# ps2.net
KiCad netlist of a schematic drawn in EAGLE
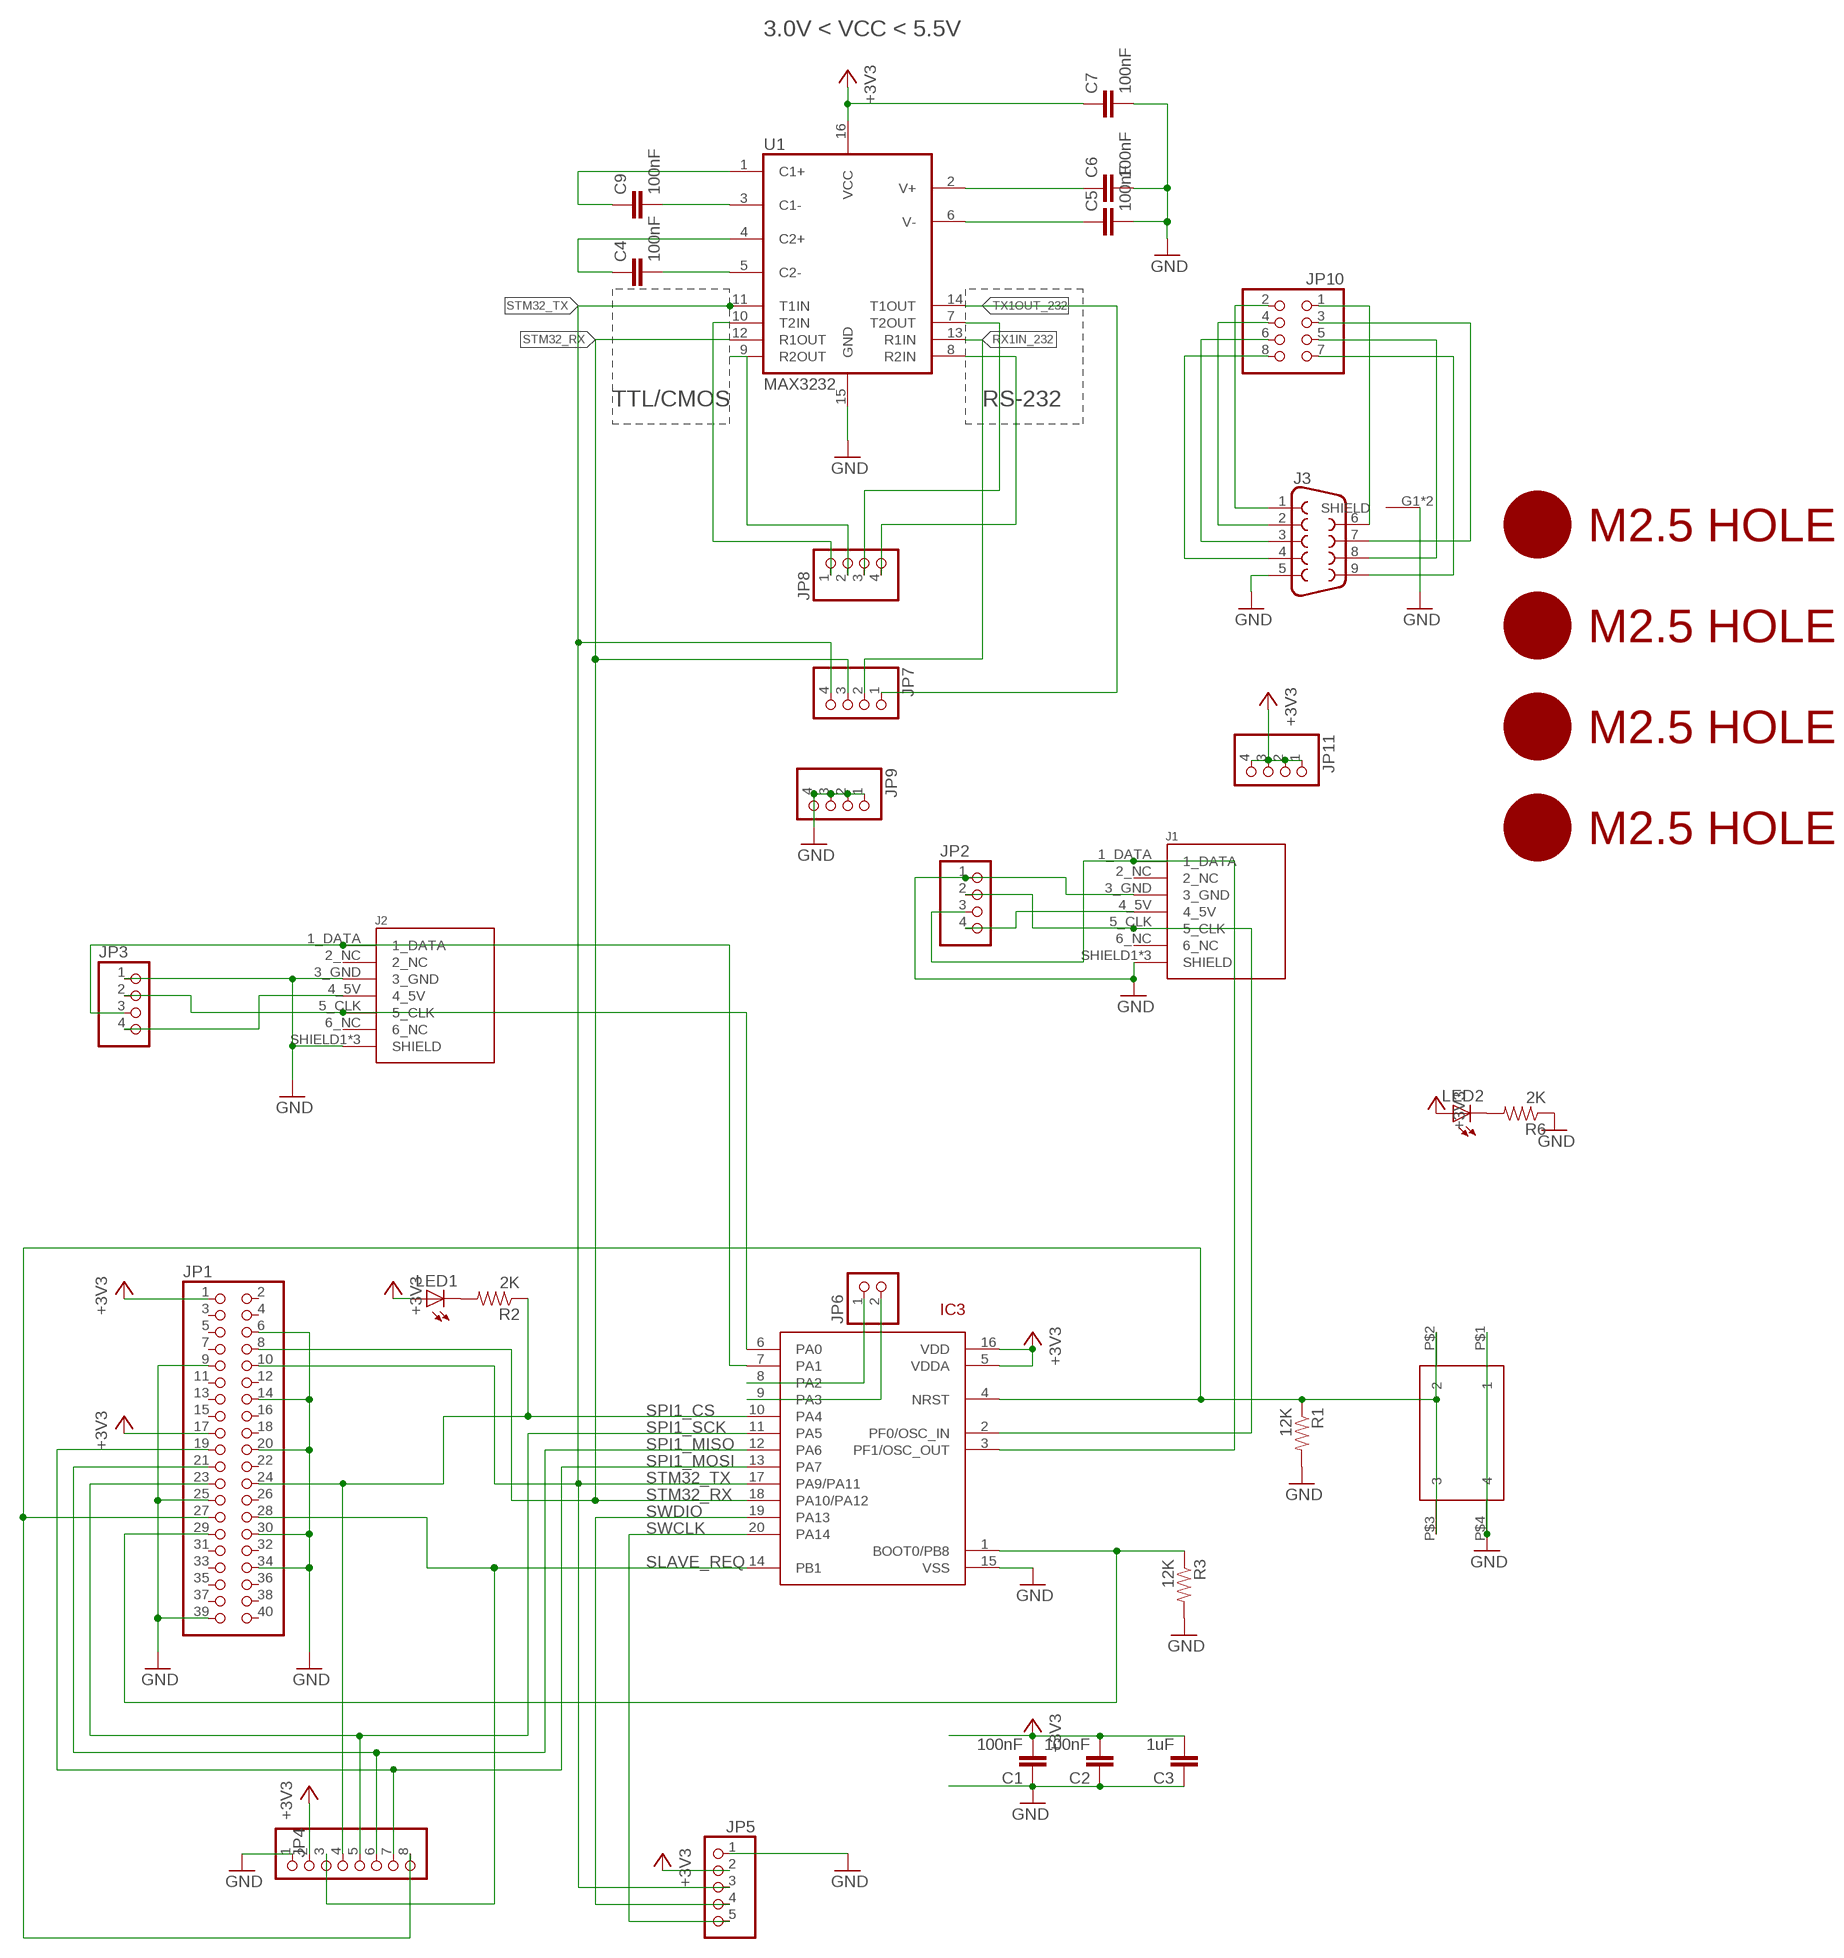
[diagram p0: schematic, sheet 1]

(export (version "E")
  (design (tool "Eeschema 10.0.6"))
  (components
    (comp (ref "C1")
      (value "100nF")
      (footprint "eagle-import:0805@1")
      (libsource (lib "eagle-import") (part "CAP0805"))
    )
    (comp (ref "C2")
      (value "100nF")
      (footprint "eagle-import:0805@1")
      (libsource (lib "eagle-import") (part "CAP0805"))
    )
    (comp (ref "C3")
      (value "1uF")
      (footprint "eagle-import:0805@1")
      (libsource (lib "eagle-import") (part "CAP0805"))
    )
    (comp (ref "C4")
      (value "100nF")
      (footprint "eagle-import:0805@1")
      (libsource (lib "eagle-import") (part "CAP0805"))
    )
    (comp (ref "C5")
      (value "100nF")
      (footprint "eagle-import:0805@1")
      (libsource (lib "eagle-import") (part "CAP0805"))
    )
    (comp (ref "C6")
      (value "100nF")
      (footprint "eagle-import:0805@1")
      (libsource (lib "eagle-import") (part "CAP0805"))
    )
    (comp (ref "C7")
      (value "100nF")
      (footprint "eagle-import:0805@1")
      (libsource (lib "eagle-import") (part "CAP0805"))
    )
    (comp (ref "C9")
      (value "100nF")
      (footprint "eagle-import:0805@1")
      (libsource (lib "eagle-import") (part "CAP0805"))
    )
    (comp (ref "IC3")
      (value "STM32F042F4")
      (footprint "eagle-import:TSSOP20")
      (libsource (lib "eagle-import") (part "STM32F042F4"))
    )
    (comp (ref "J1")
      (value "DIN7")
      (footprint "eagle-import:DIN7")
      (libsource (lib "eagle-import") (part "DIN7"))
    )
    (comp (ref "J2")
      (value "DIN7")
      (footprint "eagle-import:DIN7")
      (libsource (lib "eagle-import") (part "DIN7"))
    )
    (comp (ref "J3")
      (value "DB9MALE")
      (footprint "eagle-import:DB9_MALE")
      (libsource (lib "eagle-import") (part "DB9MALE"))
    )
    (comp (ref "JP1")
      (value "PINHD-2X20-BIG")
      (footprint "eagle-import:2X20-BIG")
      (libsource (lib "eagle-import") (part "PINHD-2X20-BIG"))
    )
    (comp (ref "JP2")
      (value "PINHD-1X4")
      (footprint "eagle-import:1X04")
      (libsource (lib "eagle-import") (part "PINHD-1X4"))
    )
    (comp (ref "JP3")
      (value "PINHD-1X4")
      (footprint "eagle-import:1X04")
      (libsource (lib "eagle-import") (part "PINHD-1X4"))
    )
    (comp (ref "JP4")
      (value "PINHD-1X8")
      (footprint "eagle-import:1X08")
      (libsource (lib "eagle-import") (part "PINHD-1X8"))
    )
    (comp (ref "JP5")
      (value "PINHD-1X5")
      (footprint "eagle-import:1X05")
      (libsource (lib "eagle-import") (part "PINHD-1X5"))
    )
    (comp (ref "JP6")
      (value "PINHD-1X2")
      (footprint "eagle-import:1X02")
      (libsource (lib "eagle-import") (part "PINHD-1X2"))
    )
    (comp (ref "JP7")
      (value "PINHD-1X4")
      (footprint "eagle-import:1X04")
      (libsource (lib "eagle-import") (part "PINHD-1X4"))
    )
    (comp (ref "JP8")
      (value "PINHD-1X4")
      (footprint "eagle-import:1X04")
      (libsource (lib "eagle-import") (part "PINHD-1X4"))
    )
    (comp (ref "JP9")
      (value "PINHD-1X4")
      (footprint "eagle-import:1X04")
      (libsource (lib "eagle-import") (part "PINHD-1X4"))
    )
    (comp (ref "JP10")
      (value "PINHD-2X4")
      (footprint "eagle-import:2X04")
      (libsource (lib "eagle-import") (part "PINHD-2X4"))
    )
    (comp (ref "JP11")
      (value "PINHD-1X4")
      (footprint "eagle-import:1X04")
      (libsource (lib "eagle-import") (part "PINHD-1X4"))
    )
    (comp (ref "LED1")
      (value "LEDCHIP-LED0805")
      (footprint "eagle-import:CHIP-LED0805")
      (libsource (lib "eagle-import") (part "LEDCHIP-LED0805"))
    )
    (comp (ref "LED2")
      (value "LEDCHIP-LED0805")
      (footprint "eagle-import:CHIP-LED0805")
      (libsource (lib "eagle-import") (part "LEDCHIP-LED0805"))
    )
    (comp (ref "R1")
      (value "12K")
      (footprint "eagle-import:0805")
      (libsource (lib "eagle-import") (part "RESISTOR0805-RES"))
    )
    (comp (ref "R2")
      (value "2K")
      (footprint "eagle-import:0805")
      (libsource (lib "eagle-import") (part "RESISTOR0805-RES"))
    )
    (comp (ref "R3")
      (value "12K")
      (footprint "eagle-import:0805")
      (libsource (lib "eagle-import") (part "RESISTOR0805-RES"))
    )
    (comp (ref "R6")
      (value "2K")
      (footprint "eagle-import:0805")
      (libsource (lib "eagle-import") (part "RESISTOR0805-RES"))
    )
    (comp (ref "SW4")
      (value "324_SW")
      (footprint "eagle-import:342_SWICH_FOOT")
      (libsource (lib "eagle-import") (part "324_SW"))
    )
    (comp (ref "U$2")
      (value "M2.5HOLE")
      (footprint "eagle-import:M2.5HOLE")
      (libsource (lib "eagle-import") (part "M2.5HOLE"))
    )
    (comp (ref "U$3")
      (value "M2.5HOLE")
      (footprint "eagle-import:M2.5HOLE")
      (libsource (lib "eagle-import") (part "M2.5HOLE"))
    )
    (comp (ref "U$4")
      (value "M2.5HOLE")
      (footprint "eagle-import:M2.5HOLE")
      (libsource (lib "eagle-import") (part "M2.5HOLE"))
    )
    (comp (ref "U$5")
      (value "M2.5HOLE")
      (footprint "eagle-import:M2.5HOLE")
      (libsource (lib "eagle-import") (part "M2.5HOLE"))
    )
    (comp (ref "U1")
      (value "MAX3232")
      (footprint "eagle-import:SO016")
      (libsource (lib "eagle-import") (part "MAX232SOIC16"))
    )
  )
  (nets
    (net (code "1") (name "+3V3") (class "Default")
      (node (ref "C1") (pin "2") (pinfunction "2_2") (pintype "passive"))
      (node (ref "C2") (pin "2") (pinfunction "2_2") (pintype "passive"))
      (node (ref "C3") (pin "2") (pinfunction "2_2") (pintype "passive"))
      (node (ref "C7") (pin "1") (pinfunction "1_1") (pintype "passive"))
      (node (ref "IC3") (pin "16") (pinfunction "VDD_16") (pintype "bidirectional"))
      (node (ref "IC3") (pin "5") (pinfunction "VDDA_5") (pintype "bidirectional"))
      (node (ref "JP1") (pin "1") (pinfunction "1_1") (pintype "passive"))
      (node (ref "JP1") (pin "17") (pinfunction "17_17") (pintype "passive"))
      (node (ref "JP11") (pin "1") (pinfunction "1_1") (pintype "passive"))
      (node (ref "JP11") (pin "2") (pinfunction "2_2") (pintype "passive"))
      (node (ref "JP11") (pin "3") (pinfunction "3_3") (pintype "passive"))
      (node (ref "JP11") (pin "4") (pinfunction "4_4") (pintype "passive"))
      (node (ref "JP4") (pin "2") (pinfunction "2_2") (pintype "passive"))
      (node (ref "JP5") (pin "2") (pinfunction "2_2") (pintype "passive"))
      (node (ref "LED1") (pin "A") (pinfunction "A_A") (pintype "passive"))
      (node (ref "LED2") (pin "A") (pinfunction "A_A") (pintype "passive"))
      (node (ref "U1") (pin "16") (pinfunction "VCC_16") (pintype "bidirectional"))
    )
    (net (code "2") (name "/SLAVE_REQ") (class "Default")
      (node (ref "IC3") (pin "14") (pinfunction "PB1_14") (pintype "bidirectional"))
      (node (ref "JP1") (pin "28") (pinfunction "28_28") (pintype "passive"))
      (node (ref "JP4") (pin "3") (pinfunction "3_3") (pintype "passive"))
    )
    (net (code "3") (name "/SPI1_CS") (class "Default")
      (node (ref "IC3") (pin "10") (pinfunction "PA4_10") (pintype "bidirectional"))
      (node (ref "JP1") (pin "24") (pinfunction "24_24") (pintype "passive"))
      (node (ref "JP4") (pin "4") (pinfunction "4_4") (pintype "passive"))
      (node (ref "R2") (pin "1") (pinfunction "1_1") (pintype "passive"))
    )
    (net (code "4") (name "/SPI1_MISO") (class "Default")
      (node (ref "IC3") (pin "12") (pinfunction "PA6_12") (pintype "bidirectional"))
      (node (ref "JP1") (pin "21") (pinfunction "21_21") (pintype "passive"))
      (node (ref "JP4") (pin "6") (pinfunction "6_6") (pintype "passive"))
    )
    (net (code "5") (name "/SPI1_MOSI") (class "Default")
      (node (ref "IC3") (pin "13") (pinfunction "PA7_13") (pintype "bidirectional"))
      (node (ref "JP1") (pin "19") (pinfunction "19_19") (pintype "passive"))
      (node (ref "JP4") (pin "7") (pinfunction "7_7") (pintype "passive"))
    )
    (net (code "6") (name "/SPI1_SCK") (class "Default")
      (node (ref "IC3") (pin "11") (pinfunction "PA5_11") (pintype "bidirectional"))
      (node (ref "JP1") (pin "23") (pinfunction "23_23") (pintype "passive"))
      (node (ref "JP4") (pin "5") (pinfunction "5_5") (pintype "passive"))
    )
    (net (code "7") (name "/SWCLK") (class "Default")
      (node (ref "IC3") (pin "20") (pinfunction "PA14_20") (pintype "bidirectional"))
      (node (ref "JP5") (pin "5") (pinfunction "5_5") (pintype "passive"))
    )
    (net (code "8") (name "/SWDIO") (class "Default")
      (node (ref "IC3") (pin "19") (pinfunction "PA13_19") (pintype "bidirectional"))
      (node (ref "JP5") (pin "4") (pinfunction "4_4") (pintype "passive"))
    )
    (net (code "9") (name "GND") (class "Default")
      (node (ref "C1") (pin "1") (pinfunction "1_1") (pintype "passive"))
      (node (ref "C2") (pin "1") (pinfunction "1_1") (pintype "passive"))
      (node (ref "C3") (pin "1") (pinfunction "1_1") (pintype "passive"))
      (node (ref "C5") (pin "2") (pinfunction "2_2") (pintype "passive"))
      (node (ref "C6") (pin "2") (pinfunction "2_2") (pintype "passive"))
      (node (ref "C7") (pin "2") (pinfunction "2_2") (pintype "passive"))
      (node (ref "IC3") (pin "15") (pinfunction "VSS_15") (pintype "bidirectional"))
      (node (ref "J1") (pin "3_GND") (pinfunction "3_GND_3_GND") (pintype "bidirectional"))
      (node (ref "J1") (pin "SHIELD1") (pinfunction "SHIELD_SHIELD1") (pintype "bidirectional"))
      (node (ref "J1") (pin "SHIELD2") (pinfunction "SHIELD_SHIELD2") (pintype "bidirectional"))
      (node (ref "J1") (pin "SHIELD3") (pinfunction "SHIELD_SHIELD3") (pintype "bidirectional"))
      (node (ref "J2") (pin "3_GND") (pinfunction "3_GND_3_GND") (pintype "bidirectional"))
      (node (ref "J2") (pin "SHIELD1") (pinfunction "SHIELD_SHIELD1") (pintype "bidirectional"))
      (node (ref "J2") (pin "SHIELD2") (pinfunction "SHIELD_SHIELD2") (pintype "bidirectional"))
      (node (ref "J2") (pin "SHIELD3") (pinfunction "SHIELD_SHIELD3") (pintype "bidirectional"))
      (node (ref "J3") (pin "5") (pinfunction "5_5") (pintype "passive"))
      (node (ref "J3") (pin "G1") (pinfunction "SHIELD_G1") (pintype "bidirectional"))
      (node (ref "J3") (pin "G2") (pinfunction "SHIELD_G2") (pintype "bidirectional"))
      (node (ref "JP1") (pin "14") (pinfunction "14_14") (pintype "passive"))
      (node (ref "JP1") (pin "20") (pinfunction "20_20") (pintype "passive"))
      (node (ref "JP1") (pin "25") (pinfunction "25_25") (pintype "passive"))
      (node (ref "JP1") (pin "30") (pinfunction "30_30") (pintype "passive"))
      (node (ref "JP1") (pin "34") (pinfunction "34_34") (pintype "passive"))
      (node (ref "JP1") (pin "39") (pinfunction "39_39") (pintype "passive"))
      (node (ref "JP1") (pin "6") (pinfunction "6_6") (pintype "passive"))
      (node (ref "JP1") (pin "9") (pinfunction "9_9") (pintype "passive"))
      (node (ref "JP2") (pin "1") (pinfunction "1_1") (pintype "passive"))
      (node (ref "JP3") (pin "1") (pinfunction "1_1") (pintype "passive"))
      (node (ref "JP4") (pin "1") (pinfunction "1_1") (pintype "passive"))
      (node (ref "JP5") (pin "1") (pinfunction "1_1") (pintype "passive"))
      (node (ref "JP9") (pin "1") (pinfunction "1_1") (pintype "passive"))
      (node (ref "JP9") (pin "2") (pinfunction "2_2") (pintype "passive"))
      (node (ref "JP9") (pin "3") (pinfunction "3_3") (pintype "passive"))
      (node (ref "JP9") (pin "4") (pinfunction "4_4") (pintype "passive"))
      (node (ref "R1") (pin "2") (pinfunction "2_2") (pintype "passive"))
      (node (ref "R3") (pin "2") (pinfunction "2_2") (pintype "passive"))
      (node (ref "R6") (pin "1") (pinfunction "1_1") (pintype "passive"))
      (node (ref "SW4") (pin "P$1") (pinfunction "1_P$1") (pintype "bidirectional"))
      (node (ref "SW4") (pin "P$4") (pinfunction "4_P$4") (pintype "bidirectional"))
      (node (ref "U1") (pin "15") (pinfunction "GND_15") (pintype "bidirectional"))
    )
    (net (code "10") (name "Net-(IC3-BOOT0{slash}PB8)") (class "Default")
      (node (ref "IC3") (pin "1") (pinfunction "BOOT0/PB8_1") (pintype "bidirectional"))
      (node (ref "JP1") (pin "29") (pinfunction "29_29") (pintype "passive"))
      (node (ref "R3") (pin "1") (pinfunction "1_1") (pintype "passive"))
    )
    (net (code "11") (name "Net-(IC3-NRST)") (class "Default")
      (node (ref "IC3") (pin "4") (pinfunction "NRST_4") (pintype "bidirectional"))
      (node (ref "JP1") (pin "27") (pinfunction "27_27") (pintype "passive"))
      (node (ref "JP4") (pin "8") (pinfunction "8_8") (pintype "passive"))
      (node (ref "R1") (pin "1") (pinfunction "1_1") (pintype "passive"))
      (node (ref "SW4") (pin "P$2") (pinfunction "2_P$2") (pintype "bidirectional"))
      (node (ref "SW4") (pin "P$3") (pinfunction "3_P$3") (pintype "bidirectional"))
    )
    (net (code "12") (name "Net-(IC3-PA0)") (class "Default")
      (node (ref "IC3") (pin "6") (pinfunction "PA0_6") (pintype "bidirectional"))
      (node (ref "J2") (pin "5_CLK") (pinfunction "5_CLK_5_CLK") (pintype "bidirectional"))
      (node (ref "JP3") (pin "2") (pinfunction "2_2") (pintype "passive"))
    )
    (net (code "13") (name "Net-(IC3-PA1)") (class "Default")
      (node (ref "IC3") (pin "7") (pinfunction "PA1_7") (pintype "bidirectional"))
      (node (ref "J2") (pin "1_DATA") (pinfunction "1_DATA_1_DATA") (pintype "bidirectional"))
      (node (ref "JP3") (pin "3") (pinfunction "3_3") (pintype "passive"))
    )
    (net (code "14") (name "Net-(IC3-PA2)") (class "Default")
      (node (ref "IC3") (pin "8") (pinfunction "PA2_8") (pintype "bidirectional"))
      (node (ref "JP6") (pin "1") (pinfunction "1_1") (pintype "passive"))
    )
    (net (code "15") (name "Net-(IC3-PA3)") (class "Default")
      (node (ref "IC3") (pin "9") (pinfunction "PA3_9") (pintype "bidirectional"))
      (node (ref "JP6") (pin "2") (pinfunction "2_2") (pintype "passive"))
    )
    (net (code "16") (name "Net-(IC3-PF0{slash}OSC_IN)") (class "Default")
      (node (ref "IC3") (pin "2") (pinfunction "PF0/OSC_IN_2") (pintype "bidirectional"))
      (node (ref "J1") (pin "5_CLK") (pinfunction "5_CLK_5_CLK") (pintype "bidirectional"))
      (node (ref "JP2") (pin "2") (pinfunction "2_2") (pintype "passive"))
    )
    (net (code "17") (name "Net-(IC3-PF1{slash}OSC_OUT)") (class "Default")
      (node (ref "IC3") (pin "3") (pinfunction "PF1/OSC_OUT_3") (pintype "bidirectional"))
      (node (ref "J1") (pin "1_DATA") (pinfunction "1_DATA_1_DATA") (pintype "bidirectional"))
      (node (ref "JP2") (pin "3") (pinfunction "3_3") (pintype "passive"))
    )
    (net (code "18") (name "Net-(J1-Pad4_5V)") (class "Default")
      (node (ref "J1") (pin "4_5V") (pinfunction "4_5V_4_5V") (pintype "bidirectional"))
      (node (ref "JP2") (pin "4") (pinfunction "4_4") (pintype "passive"))
    )
    (net (code "19") (name "Net-(J2-Pad4_5V)") (class "Default")
      (node (ref "J2") (pin "4_5V") (pinfunction "4_5V_4_5V") (pintype "bidirectional"))
      (node (ref "JP3") (pin "4") (pinfunction "4_4") (pintype "passive"))
    )
    (net (code "20") (name "Net-(J3-Pad1)") (class "Default")
      (node (ref "J3") (pin "1") (pinfunction "1_1") (pintype "passive"))
      (node (ref "JP10") (pin "2") (pinfunction "2_2") (pintype "passive"))
    )
    (net (code "21") (name "Net-(J3-Pad2)") (class "Default")
      (node (ref "J3") (pin "2") (pinfunction "2_2") (pintype "passive"))
      (node (ref "JP10") (pin "4") (pinfunction "4_4") (pintype "passive"))
    )
    (net (code "22") (name "Net-(J3-Pad3)") (class "Default")
      (node (ref "J3") (pin "3") (pinfunction "3_3") (pintype "passive"))
      (node (ref "JP10") (pin "6") (pinfunction "6_6") (pintype "passive"))
    )
    (net (code "23") (name "Net-(J3-Pad4)") (class "Default")
      (node (ref "J3") (pin "4") (pinfunction "4_4") (pintype "passive"))
      (node (ref "JP10") (pin "8") (pinfunction "8_8") (pintype "passive"))
    )
    (net (code "24") (name "Net-(J3-Pad6)") (class "Default")
      (node (ref "J3") (pin "6") (pinfunction "6_6") (pintype "passive"))
      (node (ref "JP10") (pin "1") (pinfunction "1_1") (pintype "passive"))
    )
    (net (code "25") (name "Net-(J3-Pad7)") (class "Default")
      (node (ref "J3") (pin "7") (pinfunction "7_7") (pintype "passive"))
      (node (ref "JP10") (pin "3") (pinfunction "3_3") (pintype "passive"))
    )
    (net (code "26") (name "Net-(J3-Pad8)") (class "Default")
      (node (ref "J3") (pin "8") (pinfunction "8_8") (pintype "passive"))
      (node (ref "JP10") (pin "5") (pinfunction "5_5") (pintype "passive"))
    )
    (net (code "27") (name "Net-(J3-Pad9)") (class "Default")
      (node (ref "J3") (pin "9") (pinfunction "9_9") (pintype "passive"))
      (node (ref "JP10") (pin "7") (pinfunction "7_7") (pintype "passive"))
    )
    (net (code "28") (name "Net-(LED1-PadC)") (class "Default")
      (node (ref "LED1") (pin "C") (pinfunction "C_C") (pintype "passive"))
      (node (ref "R2") (pin "2") (pinfunction "2_2") (pintype "passive"))
    )
    (net (code "29") (name "Net-(LED2-PadC)") (class "Default")
      (node (ref "LED2") (pin "C") (pinfunction "C_C") (pintype "passive"))
      (node (ref "R6") (pin "2") (pinfunction "2_2") (pintype "passive"))
    )
    (net (code "30") (name "Net-(U1-C1+)") (class "Default")
      (node (ref "C9") (pin "1") (pinfunction "1_1") (pintype "passive"))
      (node (ref "U1") (pin "1") (pinfunction "C1+_1") (pintype "bidirectional"))
    )
    (net (code "31") (name "Net-(U1-C1-)") (class "Default")
      (node (ref "C9") (pin "2") (pinfunction "2_2") (pintype "passive"))
      (node (ref "U1") (pin "3") (pinfunction "C1-_3") (pintype "bidirectional"))
    )
    (net (code "32") (name "Net-(U1-C2+)") (class "Default")
      (node (ref "C4") (pin "1") (pinfunction "1_1") (pintype "passive"))
      (node (ref "U1") (pin "4") (pinfunction "C2+_4") (pintype "bidirectional"))
    )
    (net (code "33") (name "Net-(U1-C2-)") (class "Default")
      (node (ref "C4") (pin "2") (pinfunction "2_2") (pintype "passive"))
      (node (ref "U1") (pin "5") (pinfunction "C2-_5") (pintype "bidirectional"))
    )
    (net (code "34") (name "Net-(U1-R2IN)") (class "Default")
      (node (ref "JP8") (pin "4") (pinfunction "4_4") (pintype "passive"))
      (node (ref "U1") (pin "8") (pinfunction "R2IN_8") (pintype "input"))
    )
    (net (code "35") (name "Net-(U1-R2OUT)") (class "Default")
      (node (ref "JP8") (pin "2") (pinfunction "2_2") (pintype "passive"))
      (node (ref "U1") (pin "9") (pinfunction "R2OUT_9") (pintype "output"))
    )
    (net (code "36") (name "Net-(U1-T2IN)") (class "Default")
      (node (ref "JP8") (pin "1") (pinfunction "1_1") (pintype "passive"))
      (node (ref "U1") (pin "10") (pinfunction "T2IN_10") (pintype "input"))
    )
    (net (code "37") (name "Net-(U1-T2OUT)") (class "Default")
      (node (ref "JP8") (pin "3") (pinfunction "3_3") (pintype "passive"))
      (node (ref "U1") (pin "7") (pinfunction "T2OUT_7") (pintype "output"))
    )
    (net (code "38") (name "Net-(U1-V+)") (class "Default")
      (node (ref "C6") (pin "1") (pinfunction "1_1") (pintype "passive"))
      (node (ref "U1") (pin "2") (pinfunction "V+_2") (pintype "bidirectional"))
    )
    (net (code "39") (name "Net-(U1-V-)") (class "Default")
      (node (ref "C5") (pin "1") (pinfunction "1_1") (pintype "passive"))
      (node (ref "U1") (pin "6") (pinfunction "V-_6") (pintype "bidirectional"))
    )
    (net (code "40") (name "RX1IN_232") (class "Default")
      (node (ref "JP7") (pin "2") (pinfunction "2_2") (pintype "passive"))
      (node (ref "U1") (pin "13") (pinfunction "R1IN_13") (pintype "input"))
    )
    (net (code "41") (name "STM32_RX") (class "Default")
      (node (ref "IC3") (pin "18") (pinfunction "PA10/PA12_18") (pintype "bidirectional"))
      (node (ref "JP1") (pin "8") (pinfunction "8_8") (pintype "passive"))
      (node (ref "JP7") (pin "3") (pinfunction "3_3") (pintype "passive"))
      (node (ref "U1") (pin "12") (pinfunction "R1OUT_12") (pintype "output"))
    )
    (net (code "42") (name "STM32_TX") (class "Default")
      (node (ref "IC3") (pin "17") (pinfunction "PA9/PA11_17") (pintype "bidirectional"))
      (node (ref "JP1") (pin "10") (pinfunction "10_10") (pintype "passive"))
      (node (ref "JP5") (pin "3") (pinfunction "3_3") (pintype "passive"))
      (node (ref "JP7") (pin "4") (pinfunction "4_4") (pintype "passive"))
      (node (ref "U1") (pin "11") (pinfunction "T1IN_11") (pintype "input"))
    )
    (net (code "43") (name "TX1OUT_232") (class "Default")
      (node (ref "JP7") (pin "1") (pinfunction "1_1") (pintype "passive"))
      (node (ref "U1") (pin "14") (pinfunction "T1OUT_14") (pintype "output"))
    )
    (net (code "44") (name "unconnected-(J1-Pad2_NC)") (class "Default")
      (node (ref "J1") (pin "2_NC") (pinfunction "2_NC_2_NC") (pintype "bidirectional"))
    )
    (net (code "45") (name "unconnected-(J1-Pad6_NC)") (class "Default")
      (node (ref "J1") (pin "6_NC") (pinfunction "6_NC_6_NC") (pintype "bidirectional"))
    )
    (net (code "46") (name "unconnected-(J2-Pad2_NC)") (class "Default")
      (node (ref "J2") (pin "2_NC") (pinfunction "2_NC_2_NC") (pintype "bidirectional"))
    )
    (net (code "47") (name "unconnected-(J2-Pad6_NC)") (class "Default")
      (node (ref "J2") (pin "6_NC") (pinfunction "6_NC_6_NC") (pintype "bidirectional"))
    )
    (net (code "48") (name "unconnected-(JP1-Pad2)") (class "Default")
      (node (ref "JP1") (pin "2") (pinfunction "2_2") (pintype "passive"))
    )
    (net (code "49") (name "unconnected-(JP1-Pad3)") (class "Default")
      (node (ref "JP1") (pin "3") (pinfunction "3_3") (pintype "passive"))
    )
    (net (code "50") (name "unconnected-(JP1-Pad4)") (class "Default")
      (node (ref "JP1") (pin "4") (pinfunction "4_4") (pintype "passive"))
    )
    (net (code "51") (name "unconnected-(JP1-Pad5)") (class "Default")
      (node (ref "JP1") (pin "5") (pinfunction "5_5") (pintype "passive"))
    )
    (net (code "52") (name "unconnected-(JP1-Pad7)") (class "Default")
      (node (ref "JP1") (pin "7") (pinfunction "7_7") (pintype "passive"))
    )
    (net (code "53") (name "unconnected-(JP1-Pad11)") (class "Default")
      (node (ref "JP1") (pin "11") (pinfunction "11_11") (pintype "passive"))
    )
    (net (code "54") (name "unconnected-(JP1-Pad12)") (class "Default")
      (node (ref "JP1") (pin "12") (pinfunction "12_12") (pintype "passive"))
    )
    (net (code "55") (name "unconnected-(JP1-Pad13)") (class "Default")
      (node (ref "JP1") (pin "13") (pinfunction "13_13") (pintype "passive"))
    )
    (net (code "56") (name "unconnected-(JP1-Pad15)") (class "Default")
      (node (ref "JP1") (pin "15") (pinfunction "15_15") (pintype "passive"))
    )
    (net (code "57") (name "unconnected-(JP1-Pad16)") (class "Default")
      (node (ref "JP1") (pin "16") (pinfunction "16_16") (pintype "passive"))
    )
    (net (code "58") (name "unconnected-(JP1-Pad18)") (class "Default")
      (node (ref "JP1") (pin "18") (pinfunction "18_18") (pintype "passive"))
    )
    (net (code "59") (name "unconnected-(JP1-Pad22)") (class "Default")
      (node (ref "JP1") (pin "22") (pinfunction "22_22") (pintype "passive"))
    )
    (net (code "60") (name "unconnected-(JP1-Pad26)") (class "Default")
      (node (ref "JP1") (pin "26") (pinfunction "26_26") (pintype "passive"))
    )
    (net (code "61") (name "unconnected-(JP1-Pad31)") (class "Default")
      (node (ref "JP1") (pin "31") (pinfunction "31_31") (pintype "passive"))
    )
    (net (code "62") (name "unconnected-(JP1-Pad32)") (class "Default")
      (node (ref "JP1") (pin "32") (pinfunction "32_32") (pintype "passive"))
    )
    (net (code "63") (name "unconnected-(JP1-Pad33)") (class "Default")
      (node (ref "JP1") (pin "33") (pinfunction "33_33") (pintype "passive"))
    )
    (net (code "64") (name "unconnected-(JP1-Pad35)") (class "Default")
      (node (ref "JP1") (pin "35") (pinfunction "35_35") (pintype "passive"))
    )
    (net (code "65") (name "unconnected-(JP1-Pad36)") (class "Default")
      (node (ref "JP1") (pin "36") (pinfunction "36_36") (pintype "passive"))
    )
    (net (code "66") (name "unconnected-(JP1-Pad37)") (class "Default")
      (node (ref "JP1") (pin "37") (pinfunction "37_37") (pintype "passive"))
    )
    (net (code "67") (name "unconnected-(JP1-Pad38)") (class "Default")
      (node (ref "JP1") (pin "38") (pinfunction "38_38") (pintype "passive"))
    )
    (net (code "68") (name "unconnected-(JP1-Pad40)") (class "Default")
      (node (ref "JP1") (pin "40") (pinfunction "40_40") (pintype "passive"))
    )
  )
)
